# 3WireLCD_keypadV5.net
KiCad netlist of a schematic drawn in EAGLE
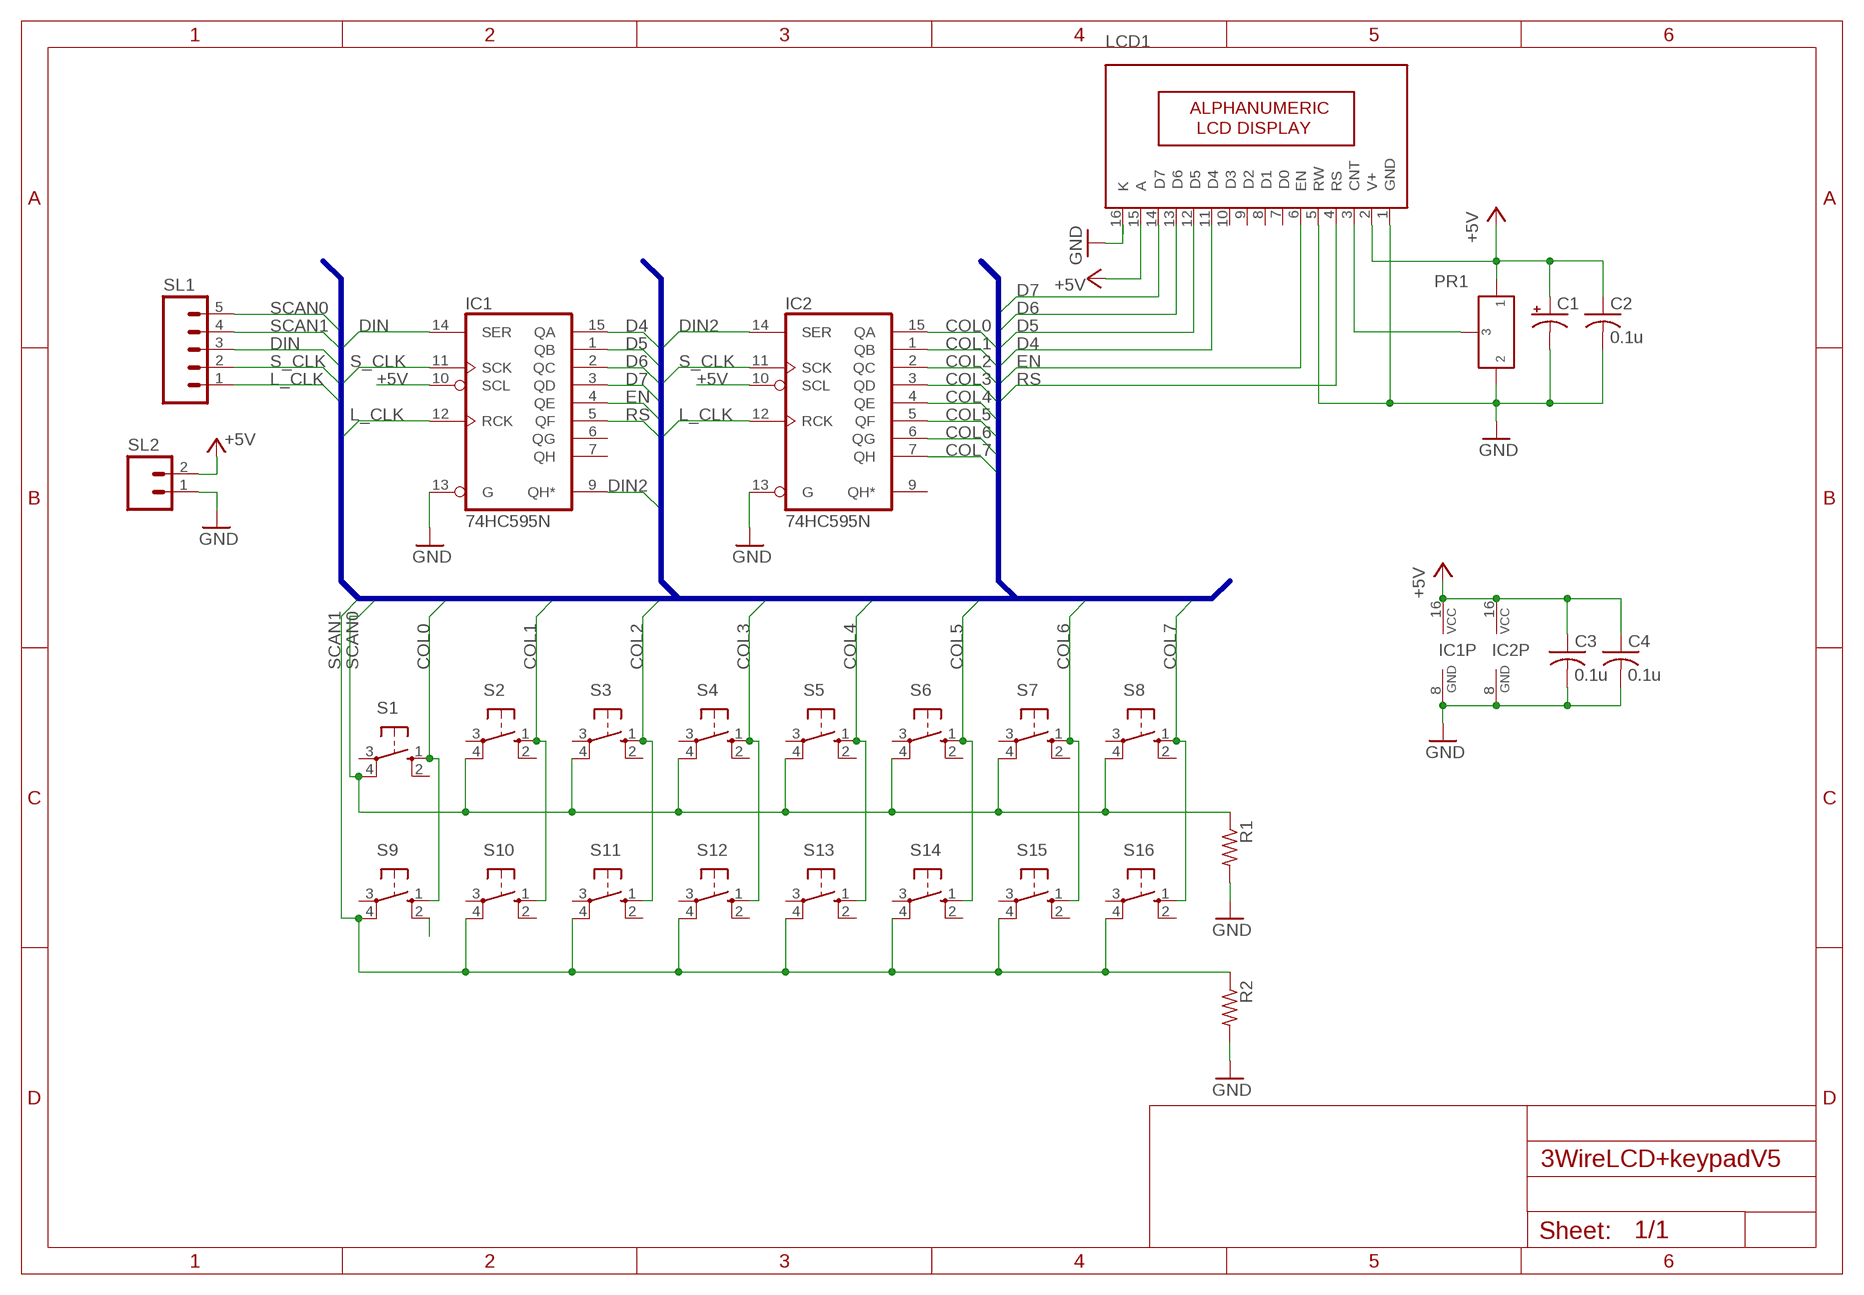
[diagram p0: schematic, sheet 1]

(export (version "E")
  (design (tool "Eeschema 10.0.6"))
  (components
    (comp (ref "C1")
      (value "CAP_POL_16V")
      (footprint "eagle-import:B_3528-21R")
      (libsource (lib "eagle-import") (part "CAP_POL_16V"))
    )
    (comp (ref "C2")
      (value "0.1u")
      (footprint "eagle-import:C0805")
      (libsource (lib "eagle-import") (part "CAP0805"))
    )
    (comp (ref "C3")
      (value "0.1u")
      (footprint "eagle-import:C0805")
      (libsource (lib "eagle-import") (part "CAP0805"))
    )
    (comp (ref "C4")
      (value "0.1u")
      (footprint "eagle-import:C0805")
      (libsource (lib "eagle-import") (part "CAP0805"))
    )
    (comp (ref "IC1")
      (value "74HC595N")
      (footprint "eagle-import:DIL16")
      (libsource (lib "eagle-import") (part "74595NHC"))
    )
    (comp (ref "IC2")
      (value "74HC595N")
      (footprint "eagle-import:DIL16")
      (libsource (lib "eagle-import") (part "74595NHC"))
    )
    (comp (ref "LCD1")
      (value "16X2LCD")
      (footprint "eagle-import:16X2_LCD")
      (libsource (lib "eagle-import") (part "16X2LCD"))
    )
    (comp (ref "R1")
      (value "RESISTOR0805")
      (footprint "eagle-import:R0805")
      (libsource (lib "eagle-import") (part "RESISTOR0805"))
    )
    (comp (ref "R2")
      (value "RESISTOR0805")
      (footprint "eagle-import:R0805")
      (libsource (lib "eagle-import") (part "RESISTOR0805"))
    )
    (comp (ref "S1")
      (value "40-XX")
      (footprint "eagle-import:B3F-40XX")
      (libsource (lib "eagle-import") (part "40-XX"))
    )
    (comp (ref "S2")
      (value "40-XX")
      (footprint "eagle-import:B3F-40XX")
      (libsource (lib "eagle-import") (part "40-XX"))
    )
    (comp (ref "S3")
      (value "40-XX")
      (footprint "eagle-import:B3F-40XX")
      (libsource (lib "eagle-import") (part "40-XX"))
    )
    (comp (ref "S4")
      (value "40-XX")
      (footprint "eagle-import:B3F-40XX")
      (libsource (lib "eagle-import") (part "40-XX"))
    )
    (comp (ref "S5")
      (value "40-XX")
      (footprint "eagle-import:B3F-40XX")
      (libsource (lib "eagle-import") (part "40-XX"))
    )
    (comp (ref "S6")
      (value "40-XX")
      (footprint "eagle-import:B3F-40XX")
      (libsource (lib "eagle-import") (part "40-XX"))
    )
    (comp (ref "S7")
      (value "40-XX")
      (footprint "eagle-import:B3F-40XX")
      (libsource (lib "eagle-import") (part "40-XX"))
    )
    (comp (ref "S8")
      (value "40-XX")
      (footprint "eagle-import:B3F-40XX")
      (libsource (lib "eagle-import") (part "40-XX"))
    )
    (comp (ref "S9")
      (value "40-XX")
      (footprint "eagle-import:B3F-40XX")
      (libsource (lib "eagle-import") (part "40-XX"))
    )
    (comp (ref "S10")
      (value "40-XX")
      (footprint "eagle-import:B3F-40XX")
      (libsource (lib "eagle-import") (part "40-XX"))
    )
    (comp (ref "S11")
      (value "40-XX")
      (footprint "eagle-import:B3F-40XX")
      (libsource (lib "eagle-import") (part "40-XX"))
    )
    (comp (ref "S12")
      (value "40-XX")
      (footprint "eagle-import:B3F-40XX")
      (libsource (lib "eagle-import") (part "40-XX"))
    )
    (comp (ref "S13")
      (value "40-XX")
      (footprint "eagle-import:B3F-40XX")
      (libsource (lib "eagle-import") (part "40-XX"))
    )
    (comp (ref "S14")
      (value "40-XX")
      (footprint "eagle-import:B3F-40XX")
      (libsource (lib "eagle-import") (part "40-XX"))
    )
    (comp (ref "S15")
      (value "40-XX")
      (footprint "eagle-import:B3F-40XX")
      (libsource (lib "eagle-import") (part "40-XX"))
    )
    (comp (ref "S16")
      (value "40-XX")
      (footprint "eagle-import:B3F-40XX")
      (libsource (lib "eagle-import") (part "40-XX"))
    )
    (comp (ref "SL1")
      (value "M05")
      (footprint "eagle-import:05P")
      (libsource (lib "eagle-import") (part "M05"))
    )
    (comp (ref "SL2")
      (value "M02")
      (footprint "eagle-import:02P")
      (libsource (lib "eagle-import") (part "M02"))
    )
    (comp (ref "U$1")
      (value "PRESET")
      (footprint "eagle-import:PRESET_PACK")
      (libsource (lib "eagle-import") (part "PRESET"))
    )
  )
  (nets
    (net (code "1") (name "+5V") (class "Default")
      (node (ref "C1") (pin "+") (pinfunction "+_+") (pintype "passive"))
      (node (ref "C2") (pin "1") (pinfunction "1_1") (pintype "passive"))
      (node (ref "C3") (pin "1") (pinfunction "1_1") (pintype "passive"))
      (node (ref "C4") (pin "1") (pinfunction "1_1") (pintype "passive"))
      (node (ref "IC1") (pin "10") (pinfunction "SCL_10") (pintype "input"))
      (node (ref "IC1") (pin "16") (pinfunction "VCC_16") (pintype "power_in"))
      (node (ref "IC2") (pin "10") (pinfunction "SCL_10") (pintype "input"))
      (node (ref "IC2") (pin "16") (pinfunction "VCC_16") (pintype "power_in"))
      (node (ref "LCD1") (pin "15") (pinfunction "A_15") (pintype "bidirectional"))
      (node (ref "LCD1") (pin "2") (pinfunction "V+_2") (pintype "bidirectional"))
      (node (ref "SL2") (pin "2") (pinfunction "2_2") (pintype "passive"))
      (node (ref "U$1") (pin "P$1") (pinfunction "1_P$1") (pintype "passive"))
    )
    (net (code "2") (name "/COL0") (class "Default")
      (node (ref "IC2") (pin "15") (pinfunction "QA_15") (pintype "tri_state"))
      (node (ref "S1") (pin "1") (pinfunction "S_1") (pintype "passive"))
      (node (ref "S9") (pin "1") (pinfunction "S_1") (pintype "passive"))
    )
    (net (code "3") (name "/COL1") (class "Default")
      (node (ref "IC2") (pin "1") (pinfunction "QB_1") (pintype "tri_state"))
      (node (ref "S10") (pin "1") (pinfunction "S_1") (pintype "passive"))
      (node (ref "S2") (pin "1") (pinfunction "S_1") (pintype "passive"))
    )
    (net (code "4") (name "/COL2") (class "Default")
      (node (ref "IC2") (pin "2") (pinfunction "QC_2") (pintype "tri_state"))
      (node (ref "S11") (pin "1") (pinfunction "S_1") (pintype "passive"))
      (node (ref "S3") (pin "1") (pinfunction "S_1") (pintype "passive"))
    )
    (net (code "5") (name "/COL3") (class "Default")
      (node (ref "IC2") (pin "3") (pinfunction "QD_3") (pintype "tri_state"))
      (node (ref "S12") (pin "1") (pinfunction "S_1") (pintype "passive"))
      (node (ref "S4") (pin "1") (pinfunction "S_1") (pintype "passive"))
    )
    (net (code "6") (name "/COL4") (class "Default")
      (node (ref "IC2") (pin "4") (pinfunction "QE_4") (pintype "tri_state"))
      (node (ref "S13") (pin "1") (pinfunction "S_1") (pintype "passive"))
      (node (ref "S5") (pin "1") (pinfunction "S_1") (pintype "passive"))
    )
    (net (code "7") (name "/COL5") (class "Default")
      (node (ref "IC2") (pin "5") (pinfunction "QF_5") (pintype "tri_state"))
      (node (ref "S14") (pin "1") (pinfunction "S_1") (pintype "passive"))
      (node (ref "S6") (pin "1") (pinfunction "S_1") (pintype "passive"))
    )
    (net (code "8") (name "/COL6") (class "Default")
      (node (ref "IC2") (pin "6") (pinfunction "QG_6") (pintype "tri_state"))
      (node (ref "S15") (pin "1") (pinfunction "S_1") (pintype "passive"))
      (node (ref "S7") (pin "1") (pinfunction "S_1") (pintype "passive"))
    )
    (net (code "9") (name "/COL7") (class "Default")
      (node (ref "IC2") (pin "7") (pinfunction "QH_7") (pintype "tri_state"))
      (node (ref "S16") (pin "1") (pinfunction "S_1") (pintype "passive"))
      (node (ref "S8") (pin "1") (pinfunction "S_1") (pintype "passive"))
    )
    (net (code "10") (name "/D4") (class "Default")
      (node (ref "IC1") (pin "15") (pinfunction "QA_15") (pintype "tri_state"))
      (node (ref "LCD1") (pin "11") (pinfunction "D4_11") (pintype "bidirectional"))
    )
    (net (code "11") (name "/D5") (class "Default")
      (node (ref "IC1") (pin "1") (pinfunction "QB_1") (pintype "tri_state"))
      (node (ref "LCD1") (pin "12") (pinfunction "D5_12") (pintype "bidirectional"))
    )
    (net (code "12") (name "/D6") (class "Default")
      (node (ref "IC1") (pin "2") (pinfunction "QC_2") (pintype "tri_state"))
      (node (ref "LCD1") (pin "13") (pinfunction "D6_13") (pintype "bidirectional"))
    )
    (net (code "13") (name "/D7") (class "Default")
      (node (ref "IC1") (pin "3") (pinfunction "QD_3") (pintype "tri_state"))
      (node (ref "LCD1") (pin "14") (pinfunction "D7_14") (pintype "bidirectional"))
    )
    (net (code "14") (name "/DIN") (class "Default")
      (node (ref "IC1") (pin "14") (pinfunction "SER_14") (pintype "input"))
      (node (ref "SL1") (pin "3") (pinfunction "3_3") (pintype "passive"))
    )
    (net (code "15") (name "/DIN2") (class "Default")
      (node (ref "IC1") (pin "9") (pinfunction "QH*_9") (pintype "tri_state"))
      (node (ref "IC2") (pin "14") (pinfunction "SER_14") (pintype "input"))
    )
    (net (code "16") (name "/EN") (class "Default")
      (node (ref "IC1") (pin "4") (pinfunction "QE_4") (pintype "tri_state"))
      (node (ref "LCD1") (pin "6") (pinfunction "EN_6") (pintype "bidirectional"))
    )
    (net (code "17") (name "/L_CLK") (class "Default")
      (node (ref "IC1") (pin "12") (pinfunction "RCK_12") (pintype "input"))
      (node (ref "IC2") (pin "12") (pinfunction "RCK_12") (pintype "input"))
      (node (ref "SL1") (pin "1") (pinfunction "1_1") (pintype "passive"))
    )
    (net (code "18") (name "/RS") (class "Default")
      (node (ref "IC1") (pin "5") (pinfunction "QF_5") (pintype "tri_state"))
      (node (ref "LCD1") (pin "4") (pinfunction "RS_4") (pintype "bidirectional"))
    )
    (net (code "19") (name "/SCAN0") (class "Default")
      (node (ref "R1") (pin "1") (pinfunction "1_1") (pintype "passive"))
      (node (ref "S1") (pin "4") (pinfunction "P1_4") (pintype "passive"))
      (node (ref "S2") (pin "4") (pinfunction "P1_4") (pintype "passive"))
      (node (ref "S3") (pin "4") (pinfunction "P1_4") (pintype "passive"))
      (node (ref "S4") (pin "4") (pinfunction "P1_4") (pintype "passive"))
      (node (ref "S5") (pin "4") (pinfunction "P1_4") (pintype "passive"))
      (node (ref "S6") (pin "4") (pinfunction "P1_4") (pintype "passive"))
      (node (ref "S7") (pin "4") (pinfunction "P1_4") (pintype "passive"))
      (node (ref "S8") (pin "4") (pinfunction "P1_4") (pintype "passive"))
      (node (ref "SL1") (pin "5") (pinfunction "5_5") (pintype "passive"))
    )
    (net (code "20") (name "/SCAN1") (class "Default")
      (node (ref "R2") (pin "1") (pinfunction "1_1") (pintype "passive"))
      (node (ref "S10") (pin "4") (pinfunction "P1_4") (pintype "passive"))
      (node (ref "S11") (pin "4") (pinfunction "P1_4") (pintype "passive"))
      (node (ref "S12") (pin "4") (pinfunction "P1_4") (pintype "passive"))
      (node (ref "S13") (pin "4") (pinfunction "P1_4") (pintype "passive"))
      (node (ref "S14") (pin "4") (pinfunction "P1_4") (pintype "passive"))
      (node (ref "S15") (pin "4") (pinfunction "P1_4") (pintype "passive"))
      (node (ref "S16") (pin "4") (pinfunction "P1_4") (pintype "passive"))
      (node (ref "S9") (pin "4") (pinfunction "P1_4") (pintype "passive"))
      (node (ref "SL1") (pin "4") (pinfunction "4_4") (pintype "passive"))
    )
    (net (code "21") (name "/S_CLK") (class "Default")
      (node (ref "IC1") (pin "11") (pinfunction "SCK_11") (pintype "input"))
      (node (ref "IC2") (pin "11") (pinfunction "SCK_11") (pintype "input"))
      (node (ref "SL1") (pin "2") (pinfunction "2_2") (pintype "passive"))
    )
    (net (code "22") (name "GND") (class "Default")
      (node (ref "C1") (pin "-") (pinfunction "-_-") (pintype "passive"))
      (node (ref "C2") (pin "2") (pinfunction "2_2") (pintype "passive"))
      (node (ref "C3") (pin "2") (pinfunction "2_2") (pintype "passive"))
      (node (ref "C4") (pin "2") (pinfunction "2_2") (pintype "passive"))
      (node (ref "IC1") (pin "13") (pinfunction "G_13") (pintype "input"))
      (node (ref "IC1") (pin "8") (pinfunction "GND_8") (pintype "power_in"))
      (node (ref "IC2") (pin "13") (pinfunction "G_13") (pintype "input"))
      (node (ref "IC2") (pin "8") (pinfunction "GND_8") (pintype "power_in"))
      (node (ref "LCD1") (pin "1") (pinfunction "GND_1") (pintype "bidirectional"))
      (node (ref "LCD1") (pin "16") (pinfunction "K_16") (pintype "bidirectional"))
      (node (ref "LCD1") (pin "5") (pinfunction "RW_5") (pintype "bidirectional"))
      (node (ref "R1") (pin "2") (pinfunction "2_2") (pintype "passive"))
      (node (ref "R2") (pin "2") (pinfunction "2_2") (pintype "passive"))
      (node (ref "SL2") (pin "1") (pinfunction "1_1") (pintype "passive"))
      (node (ref "U$1") (pin "P$2") (pinfunction "2_P$2") (pintype "passive"))
    )
    (net (code "23") (name "Net-(LCD1-CNT)") (class "Default")
      (node (ref "LCD1") (pin "3") (pinfunction "CNT_3") (pintype "bidirectional"))
      (node (ref "U$1") (pin "P$3") (pinfunction "3_P$3") (pintype "passive"))
    )
    (net (code "24") (name "unconnected-(IC1A-QG-Pad6)") (class "Default")
      (node (ref "IC1") (pin "6") (pinfunction "QG_6") (pintype "tri_state"))
    )
    (net (code "25") (name "unconnected-(IC1A-QH-Pad7)") (class "Default")
      (node (ref "IC1") (pin "7") (pinfunction "QH_7") (pintype "tri_state"))
    )
    (net (code "26") (name "unconnected-(IC2A-QH*-Pad9)") (class "Default")
      (node (ref "IC2") (pin "9") (pinfunction "QH*_9") (pintype "tri_state"))
    )
    (net (code "27") (name "unconnected-(LCD1-D0-Pad7)") (class "Default")
      (node (ref "LCD1") (pin "7") (pinfunction "D0_7") (pintype "bidirectional"))
    )
    (net (code "28") (name "unconnected-(LCD1-D1-Pad8)") (class "Default")
      (node (ref "LCD1") (pin "8") (pinfunction "D1_8") (pintype "bidirectional"))
    )
    (net (code "29") (name "unconnected-(LCD1-D2-Pad9)") (class "Default")
      (node (ref "LCD1") (pin "9") (pinfunction "D2_9") (pintype "bidirectional"))
    )
    (net (code "30") (name "unconnected-(LCD1-D3-Pad10)") (class "Default")
      (node (ref "LCD1") (pin "10") (pinfunction "D3_10") (pintype "bidirectional"))
    )
    (net (code "31") (name "unconnected-(S1-P-Pad3)") (class "Default")
      (node (ref "S1") (pin "3") (pinfunction "P_3") (pintype "passive"))
    )
    (net (code "32") (name "unconnected-(S1-S1-Pad2)") (class "Default")
      (node (ref "S1") (pin "2") (pinfunction "S1_2") (pintype "passive"))
    )
    (net (code "33") (name "unconnected-(S2-P-Pad3)") (class "Default")
      (node (ref "S2") (pin "3") (pinfunction "P_3") (pintype "passive"))
    )
    (net (code "34") (name "unconnected-(S2-S1-Pad2)") (class "Default")
      (node (ref "S2") (pin "2") (pinfunction "S1_2") (pintype "passive"))
    )
    (net (code "35") (name "unconnected-(S3-P-Pad3)") (class "Default")
      (node (ref "S3") (pin "3") (pinfunction "P_3") (pintype "passive"))
    )
    (net (code "36") (name "unconnected-(S3-S1-Pad2)") (class "Default")
      (node (ref "S3") (pin "2") (pinfunction "S1_2") (pintype "passive"))
    )
    (net (code "37") (name "unconnected-(S4-P-Pad3)") (class "Default")
      (node (ref "S4") (pin "3") (pinfunction "P_3") (pintype "passive"))
    )
    (net (code "38") (name "unconnected-(S4-S1-Pad2)") (class "Default")
      (node (ref "S4") (pin "2") (pinfunction "S1_2") (pintype "passive"))
    )
    (net (code "39") (name "unconnected-(S5-P-Pad3)") (class "Default")
      (node (ref "S5") (pin "3") (pinfunction "P_3") (pintype "passive"))
    )
    (net (code "40") (name "unconnected-(S5-S1-Pad2)") (class "Default")
      (node (ref "S5") (pin "2") (pinfunction "S1_2") (pintype "passive"))
    )
    (net (code "41") (name "unconnected-(S6-P-Pad3)") (class "Default")
      (node (ref "S6") (pin "3") (pinfunction "P_3") (pintype "passive"))
    )
    (net (code "42") (name "unconnected-(S6-S1-Pad2)") (class "Default")
      (node (ref "S6") (pin "2") (pinfunction "S1_2") (pintype "passive"))
    )
    (net (code "43") (name "unconnected-(S7-P-Pad3)") (class "Default")
      (node (ref "S7") (pin "3") (pinfunction "P_3") (pintype "passive"))
    )
    (net (code "44") (name "unconnected-(S7-S1-Pad2)") (class "Default")
      (node (ref "S7") (pin "2") (pinfunction "S1_2") (pintype "passive"))
    )
    (net (code "45") (name "unconnected-(S8-P-Pad3)") (class "Default")
      (node (ref "S8") (pin "3") (pinfunction "P_3") (pintype "passive"))
    )
    (net (code "46") (name "unconnected-(S8-S1-Pad2)") (class "Default")
      (node (ref "S8") (pin "2") (pinfunction "S1_2") (pintype "passive"))
    )
    (net (code "47") (name "unconnected-(S9-P-Pad3)") (class "Default")
      (node (ref "S9") (pin "3") (pinfunction "P_3") (pintype "passive"))
    )
    (net (code "48") (name "unconnected-(S9-S1-Pad2)") (class "Default")
      (node (ref "S9") (pin "2") (pinfunction "S1_2") (pintype "passive"))
    )
    (net (code "49") (name "unconnected-(S10-P-Pad3)") (class "Default")
      (node (ref "S10") (pin "3") (pinfunction "P_3") (pintype "passive"))
    )
    (net (code "50") (name "unconnected-(S10-S1-Pad2)") (class "Default")
      (node (ref "S10") (pin "2") (pinfunction "S1_2") (pintype "passive"))
    )
    (net (code "51") (name "unconnected-(S11-P-Pad3)") (class "Default")
      (node (ref "S11") (pin "3") (pinfunction "P_3") (pintype "passive"))
    )
    (net (code "52") (name "unconnected-(S11-S1-Pad2)") (class "Default")
      (node (ref "S11") (pin "2") (pinfunction "S1_2") (pintype "passive"))
    )
    (net (code "53") (name "unconnected-(S12-P-Pad3)") (class "Default")
      (node (ref "S12") (pin "3") (pinfunction "P_3") (pintype "passive"))
    )
    (net (code "54") (name "unconnected-(S12-S1-Pad2)") (class "Default")
      (node (ref "S12") (pin "2") (pinfunction "S1_2") (pintype "passive"))
    )
    (net (code "55") (name "unconnected-(S13-P-Pad3)") (class "Default")
      (node (ref "S13") (pin "3") (pinfunction "P_3") (pintype "passive"))
    )
    (net (code "56") (name "unconnected-(S13-S1-Pad2)") (class "Default")
      (node (ref "S13") (pin "2") (pinfunction "S1_2") (pintype "passive"))
    )
    (net (code "57") (name "unconnected-(S14-P-Pad3)") (class "Default")
      (node (ref "S14") (pin "3") (pinfunction "P_3") (pintype "passive"))
    )
    (net (code "58") (name "unconnected-(S14-S1-Pad2)") (class "Default")
      (node (ref "S14") (pin "2") (pinfunction "S1_2") (pintype "passive"))
    )
    (net (code "59") (name "unconnected-(S15-P-Pad3)") (class "Default")
      (node (ref "S15") (pin "3") (pinfunction "P_3") (pintype "passive"))
    )
    (net (code "60") (name "unconnected-(S15-S1-Pad2)") (class "Default")
      (node (ref "S15") (pin "2") (pinfunction "S1_2") (pintype "passive"))
    )
    (net (code "61") (name "unconnected-(S16-P-Pad3)") (class "Default")
      (node (ref "S16") (pin "3") (pinfunction "P_3") (pintype "passive"))
    )
    (net (code "62") (name "unconnected-(S16-S1-Pad2)") (class "Default")
      (node (ref "S16") (pin "2") (pinfunction "S1_2") (pintype "passive"))
    )
  )
)
